# 1_Interface.net
KiCad netlist of a schematic drawn in Altium Designer
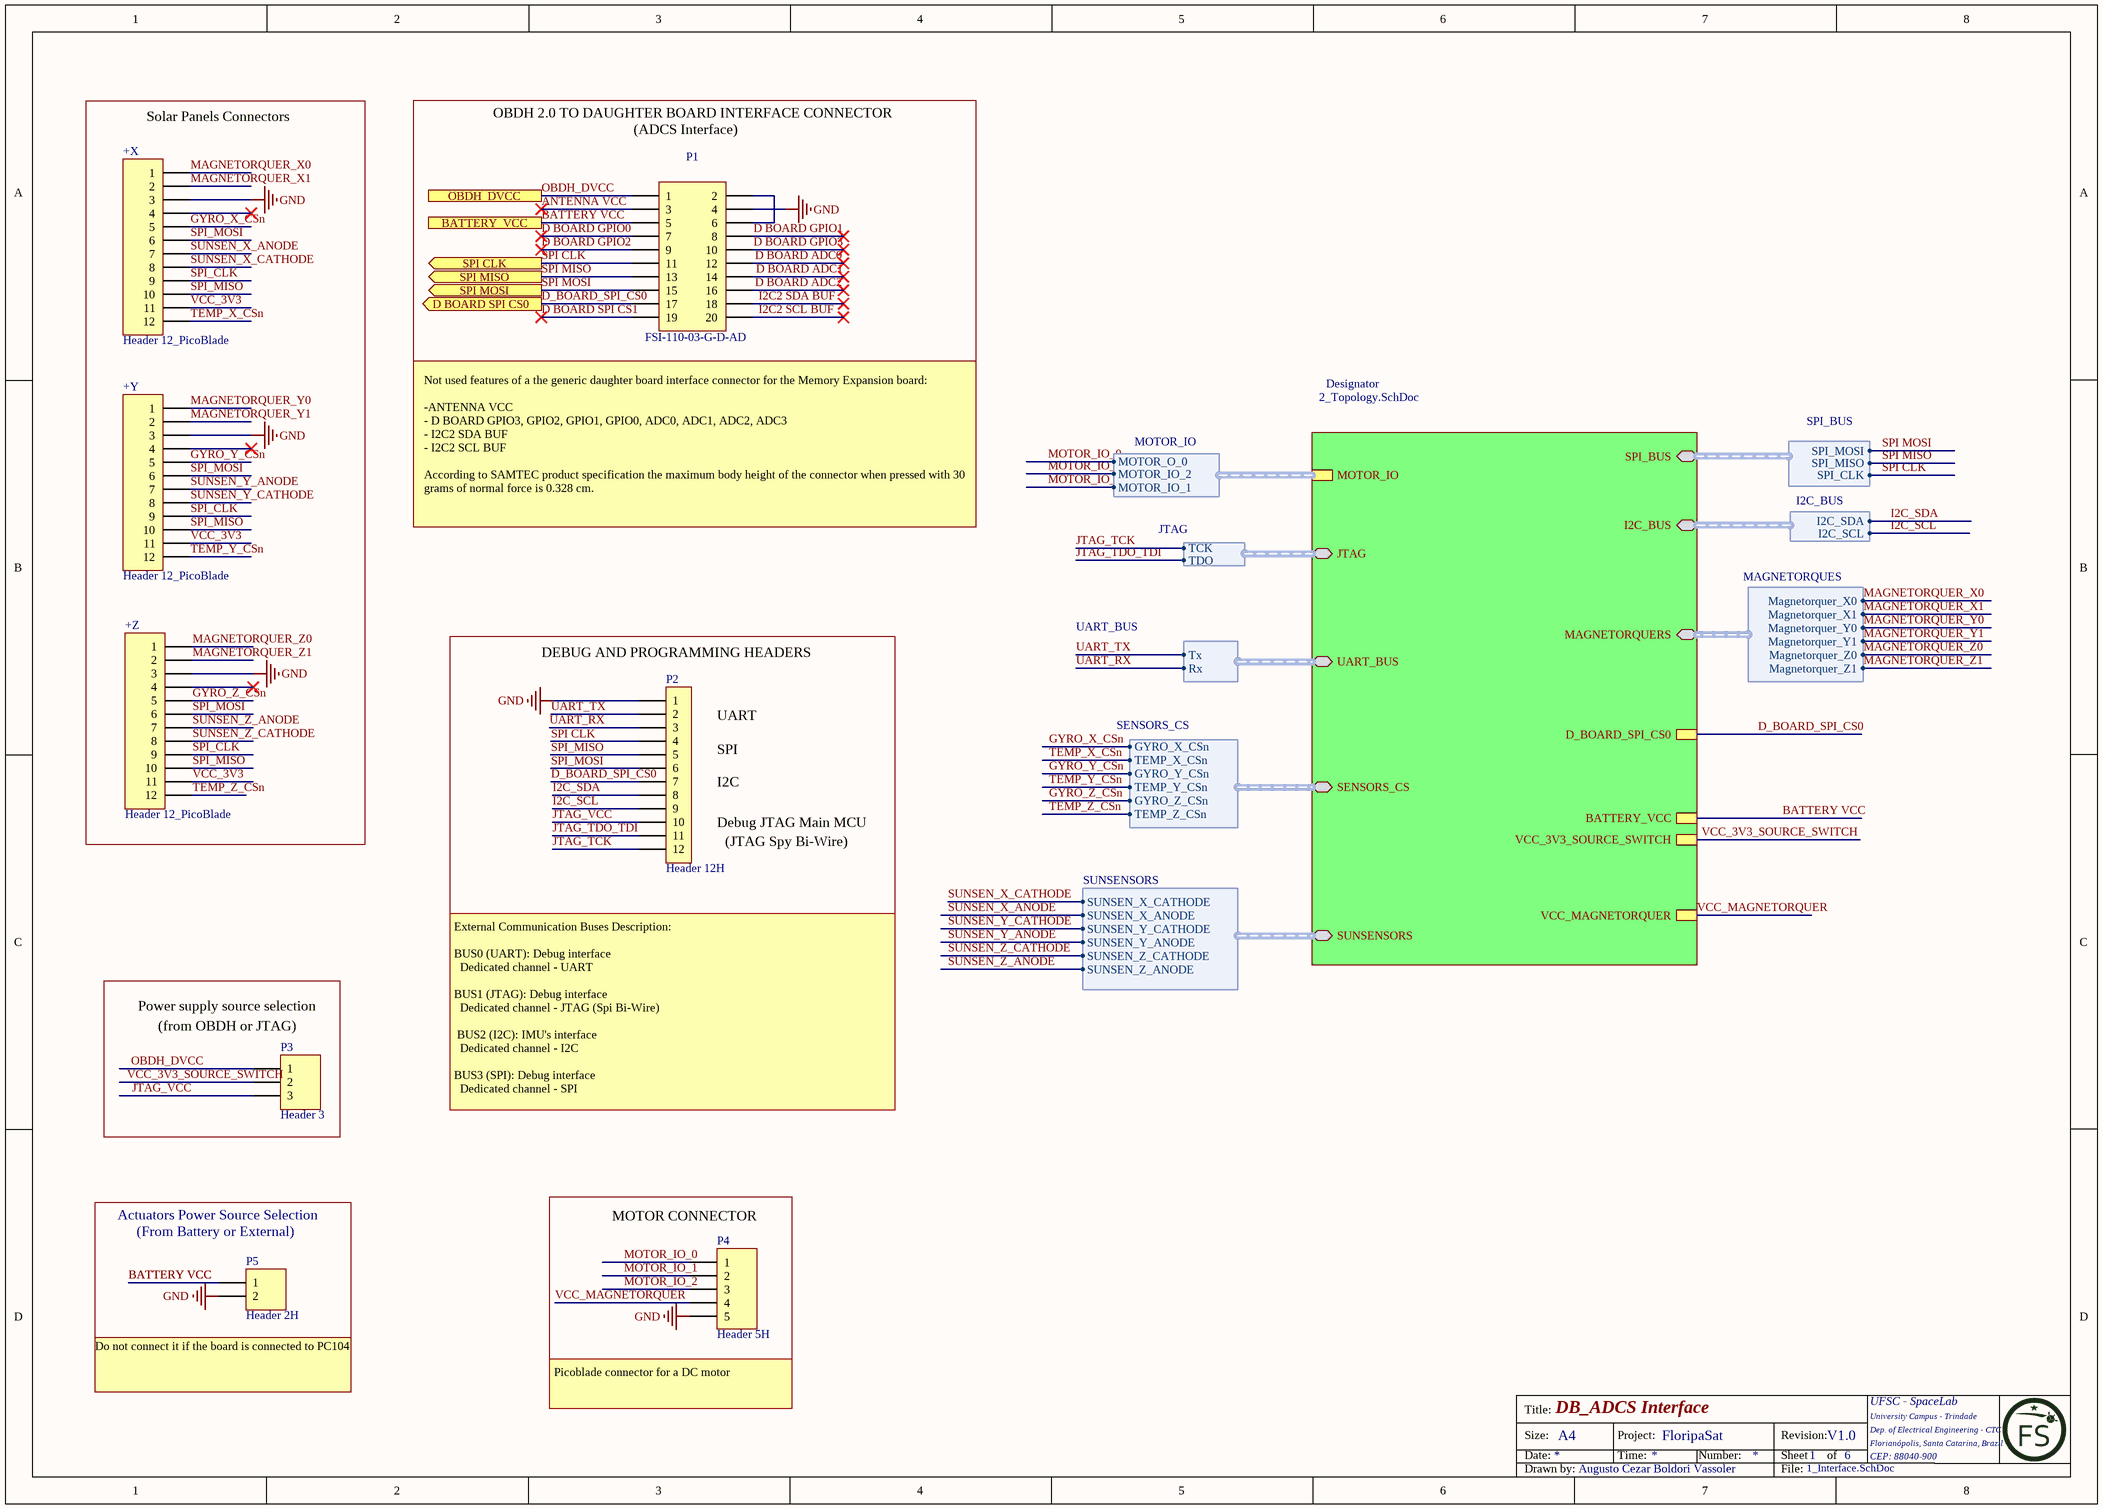
[diagram p0: 1_Interface.SchDoc]

(export (version "E")
  (design (tool "Eeschema 10.0.6"))
  (components
    (comp (ref "+X")
      (value "Header 12_PicoBlade")
      (footprint "HDR12 PicoBlade - duplicate")
      (description "Header, 12-Pin")
      (fields (field (name "PARTNUMBER") "53398-1271") (field (name "PUBLISHER") "Altium Limited"))
      (libsource (lib "FloripaSatSchlib") (part "Header 12_PicoBlade"))
    )
    (comp (ref "+Y")
      (value "Header 12_PicoBlade")
      (footprint "HDR12 PicoBlade - duplicate")
      (description "Header, 12-Pin")
      (fields (field (name "PARTNUMBER") "53398-1271") (field (name "PUBLISHER") "Altium Limited"))
      (libsource (lib "FloripaSatSchlib") (part "Header 12_PicoBlade"))
    )
    (comp (ref "+Z")
      (value "Header 12_PicoBlade")
      (footprint "HDR12 PicoBlade - duplicate")
      (description "Header, 12-Pin")
      (fields (field (name "PARTNUMBER") "533981271") (field (name "PUBLISHER") "Altium Limited"))
      (libsource (lib "FloripaSatSchlib") (part "Header 12_PicoBlade"))
    )
    (comp (ref "P1")
      (value "FSI-110-03-G-D-AD")
      (footprint "Mating FSI-110-03-G-D-AD")
      (description "CONN STACKING 20POS SMD GOLD")
      (fields (field (name "MANUFACTURER") "Samtec"))
      (libsource (lib "Memory_Expansion_Daughter_Board_SchLib") (part "FSI-110-03-G-D-AD"))
    )
    (comp (ref "P2")
      (value "Header 12H")
      (footprint "61301211021")
      (description "Header, 12")
      (fields
        (field (name "MANUFACTURER") "Wurth Electronics")
        (field (name "MANUFACTURER PART NUMBER") "61301211021")
      )
      (libsource (lib "PCB_DB_ADCS") (part "Header 12H"))
    )
    (comp (ref "P3")
      (value "Header 3")
      (footprint "HDR1X3")
      (description "Header, 3-Pin")
      (fields (field (name "PUBLISHER") "Altium Limited"))
      (libsource (lib "Miscellaneous Connectors") (part "Header 3"))
    )
    (comp (ref "P4")
      (value "Header 5H")
      (footprint "MOLX-53398-0571-5_V")
      (description "Header,5-Pin,Right Angle")
      (fields (field (name "MANUFACTURER") "Molex") (field (name "MANUFACTURER PART NUMBER") "53398-0571"))
      (libsource (lib "PCB_Eng_Model_OBDH_2") (part "Header 5H_PicoBlade"))
    )
    (comp (ref "P5")
      (value "Header 2H")
      (footprint "HDR1X2H")
      (description "Header, 2-Pin, Right Angle")
      (fields (field (name "PUBLISHER") "Altium Limited"))
      (libsource (lib "PCB_DB_ADCS") (part "Header 2H"))
    )
  )
  (nets
    (net (code "9") (name "/ANTENNA VCC") (class "Default")
      (node (ref "P1") (pin "3") (pinfunction "3_3") (pintype "passive+no_connect"))
    )
    (net (code "10") (name "/BATTERY VCC") (class "Default")
      (node (ref "P1") (pin "5") (pinfunction "5_5") (pintype "passive"))
      (node (ref "P5") (pin "1") (pinfunction "1_1") (pintype "passive"))
    )
    (net (code "11") (name "/D BOARD ADC0") (class "Default")
      (node (ref "P1") (pin "12") (pinfunction "12_12") (pintype "passive+no_connect"))
    )
    (net (code "12") (name "/D BOARD ADC1") (class "Default")
      (node (ref "P1") (pin "14") (pinfunction "14_14") (pintype "passive+no_connect"))
    )
    (net (code "13") (name "/D BOARD ADC2") (class "Default")
      (node (ref "P1") (pin "16") (pinfunction "16_16") (pintype "passive+no_connect"))
    )
    (net (code "14") (name "/D BOARD GPIO0") (class "Default")
      (node (ref "P1") (pin "7") (pinfunction "7_7") (pintype "passive+no_connect"))
    )
    (net (code "15") (name "/D BOARD GPIO1") (class "Default")
      (node (ref "P1") (pin "8") (pinfunction "8_8") (pintype "passive+no_connect"))
    )
    (net (code "16") (name "/D BOARD GPIO2") (class "Default")
      (node (ref "P1") (pin "9") (pinfunction "9_9") (pintype "passive+no_connect"))
    )
    (net (code "17") (name "/D BOARD GPIO3") (class "Default")
      (node (ref "P1") (pin "10") (pinfunction "10_10") (pintype "passive+no_connect"))
    )
    (net (code "18") (name "/D BOARD SPI CS1") (class "Default")
      (node (ref "P1") (pin "19") (pinfunction "19_19") (pintype "passive+no_connect"))
    )
    (net (code "19") (name "/D_BOARD_SPI_CS0") (class "Default")
      (node (ref "P1") (pin "17") (pinfunction "17_17") (pintype "passive"))
      (node (ref "P2") (pin "7") (pinfunction "7_7") (pintype "passive"))
    )
    (net (code "20") (name "/GYRO_X_CSn") (class "Default")
      (node (ref "+X") (pin "5") (pinfunction "5_5") (pintype "passive"))
    )
    (net (code "21") (name "/GYRO_Y_CSn") (class "Default")
      (node (ref "+Y") (pin "5") (pinfunction "5_5") (pintype "passive"))
    )
    (net (code "22") (name "/GYRO_Z_CSn") (class "Default")
      (node (ref "+Z") (pin "5") (pinfunction "5_5") (pintype "passive"))
    )
    (net (code "23") (name "/I2C2 SCL BUF") (class "Default")
      (node (ref "P1") (pin "20") (pinfunction "20_20") (pintype "passive+no_connect"))
    )
    (net (code "24") (name "/I2C2 SDA BUF") (class "Default")
      (node (ref "P1") (pin "18") (pinfunction "18_18") (pintype "passive+no_connect"))
    )
    (net (code "25") (name "/I2C_SCL") (class "Default")
      (node (ref "P2") (pin "9") (pinfunction "9_9") (pintype "passive"))
    )
    (net (code "26") (name "/I2C_SDA") (class "Default")
      (node (ref "P2") (pin "8") (pinfunction "8_8") (pintype "passive"))
    )
    (net (code "27") (name "/JTAG_TCK") (class "Default")
      (node (ref "P2") (pin "12") (pinfunction "12_12") (pintype "passive"))
    )
    (net (code "28") (name "/JTAG_TDO_TDI") (class "Default")
      (node (ref "P2") (pin "11") (pinfunction "11_11") (pintype "passive"))
    )
    (net (code "29") (name "/JTAG_VCC") (class "Default")
      (node (ref "P2") (pin "10") (pinfunction "10_10") (pintype "passive"))
      (node (ref "P3") (pin "3") (pinfunction "3_3") (pintype "passive"))
    )
    (net (code "30") (name "/MAGNETORQUER_X0") (class "Default")
      (node (ref "+X") (pin "1") (pinfunction "1_1") (pintype "passive"))
    )
    (net (code "31") (name "/MAGNETORQUER_X1") (class "Default")
      (node (ref "+X") (pin "2") (pinfunction "2_2") (pintype "passive"))
    )
    (net (code "32") (name "/MAGNETORQUER_Y0") (class "Default")
      (node (ref "+Y") (pin "1") (pinfunction "1_1") (pintype "passive"))
    )
    (net (code "33") (name "/MAGNETORQUER_Y1") (class "Default")
      (node (ref "+Y") (pin "2") (pinfunction "2_2") (pintype "passive"))
    )
    (net (code "34") (name "/MAGNETORQUER_Z0") (class "Default")
      (node (ref "+Z") (pin "1") (pinfunction "1_1") (pintype "passive"))
    )
    (net (code "35") (name "/MAGNETORQUER_Z1") (class "Default")
      (node (ref "+Z") (pin "2") (pinfunction "2_2") (pintype "passive"))
    )
    (net (code "36") (name "/MOTOR_IO_0") (class "Default")
      (node (ref "P4") (pin "1") (pinfunction "1_1") (pintype "passive"))
    )
    (net (code "37") (name "/MOTOR_IO_1") (class "Default")
      (node (ref "P4") (pin "2") (pinfunction "2_2") (pintype "passive"))
    )
    (net (code "38") (name "/MOTOR_IO_2") (class "Default")
      (node (ref "P4") (pin "3") (pinfunction "3_3") (pintype "passive"))
    )
    (net (code "39") (name "/OBDH_DVCC") (class "Default")
      (node (ref "P1") (pin "1") (pinfunction "1_1") (pintype "passive"))
      (node (ref "P3") (pin "1") (pinfunction "1_1") (pintype "passive"))
    )
    (net (code "40") (name "/SPI CLK") (class "Default")
      (node (ref "P1") (pin "11") (pinfunction "11_11") (pintype "passive"))
      (node (ref "P2") (pin "4") (pinfunction "4_4") (pintype "passive"))
    )
    (net (code "41") (name "/SPI MISO") (class "Default")
      (node (ref "P1") (pin "13") (pinfunction "13_13") (pintype "passive"))
    )
    (net (code "42") (name "/SPI MOSI") (class "Default")
      (node (ref "P1") (pin "15") (pinfunction "15_15") (pintype "passive"))
    )
    (net (code "43") (name "/SPI_CLK") (class "Default")
      (node (ref "+X") (pin "9") (pinfunction "9_9") (pintype "passive"))
      (node (ref "+Y") (pin "9") (pinfunction "9_9") (pintype "passive"))
      (node (ref "+Z") (pin "9") (pinfunction "9_9") (pintype "passive"))
    )
    (net (code "44") (name "/SPI_MISO") (class "Default")
      (node (ref "+X") (pin "10") (pinfunction "10_10") (pintype "passive"))
      (node (ref "+Y") (pin "10") (pinfunction "10_10") (pintype "passive"))
      (node (ref "+Z") (pin "10") (pinfunction "10_10") (pintype "passive"))
      (node (ref "P2") (pin "5") (pinfunction "5_5") (pintype "passive"))
    )
    (net (code "45") (name "/SPI_MOSI") (class "Default")
      (node (ref "+X") (pin "6") (pinfunction "6_6") (pintype "passive"))
      (node (ref "+Y") (pin "6") (pinfunction "6_6") (pintype "passive"))
      (node (ref "+Z") (pin "6") (pinfunction "6_6") (pintype "passive"))
      (node (ref "P2") (pin "6") (pinfunction "6_6") (pintype "passive"))
    )
    (net (code "46") (name "/SUNSEN_X_ANODE") (class "Default")
      (node (ref "+X") (pin "7") (pinfunction "7_7") (pintype "passive"))
    )
    (net (code "47") (name "/SUNSEN_X_CATHODE") (class "Default")
      (node (ref "+X") (pin "8") (pinfunction "8_8") (pintype "passive"))
    )
    (net (code "48") (name "/SUNSEN_Y_ANODE") (class "Default")
      (node (ref "+Y") (pin "7") (pinfunction "7_7") (pintype "passive"))
    )
    (net (code "49") (name "/SUNSEN_Y_CATHODE") (class "Default")
      (node (ref "+Y") (pin "8") (pinfunction "8_8") (pintype "passive"))
    )
    (net (code "50") (name "/SUNSEN_Z_ANODE") (class "Default")
      (node (ref "+Z") (pin "7") (pinfunction "7_7") (pintype "passive"))
    )
    (net (code "51") (name "/SUNSEN_Z_CATHODE") (class "Default")
      (node (ref "+Z") (pin "8") (pinfunction "8_8") (pintype "passive"))
    )
    (net (code "52") (name "/TEMP_X_CSn") (class "Default")
      (node (ref "+X") (pin "12") (pinfunction "12_12") (pintype "passive"))
    )
    (net (code "53") (name "/TEMP_Y_CSn") (class "Default")
      (node (ref "+Y") (pin "12") (pinfunction "12_12") (pintype "passive"))
    )
    (net (code "54") (name "/TEMP_Z_CSn") (class "Default")
      (node (ref "+Z") (pin "12") (pinfunction "12_12") (pintype "passive"))
    )
    (net (code "55") (name "/UART_RX") (class "Default")
      (node (ref "P2") (pin "3") (pinfunction "3_3") (pintype "passive"))
    )
    (net (code "56") (name "/UART_TX") (class "Default")
      (node (ref "P2") (pin "2") (pinfunction "2_2") (pintype "passive"))
    )
    (net (code "57") (name "/VCC_3V3") (class "Default")
      (node (ref "+X") (pin "11") (pinfunction "11_11") (pintype "passive"))
      (node (ref "+Y") (pin "11") (pinfunction "11_11") (pintype "passive"))
      (node (ref "+Z") (pin "11") (pinfunction "11_11") (pintype "passive"))
    )
    (net (code "58") (name "/VCC_3V3_SOURCE_SWITCH") (class "Default")
      (node (ref "P3") (pin "2") (pinfunction "2_2") (pintype "passive"))
    )
    (net (code "59") (name "/VCC_MAGNETORQUER") (class "Default")
      (node (ref "P4") (pin "4") (pinfunction "4_4") (pintype "passive"))
    )
    (net (code "68") (name "GND") (class "Default")
      (node (ref "+X") (pin "3") (pinfunction "3_3") (pintype "passive"))
      (node (ref "+Y") (pin "3") (pinfunction "3_3") (pintype "passive"))
      (node (ref "+Z") (pin "3") (pinfunction "3_3") (pintype "passive"))
      (node (ref "P1") (pin "4") (pinfunction "4_4") (pintype "passive"))
      (node (ref "P2") (pin "1") (pinfunction "1_1") (pintype "passive"))
      (node (ref "P4") (pin "5") (pinfunction "5_5") (pintype "passive"))
      (node (ref "P5") (pin "2") (pinfunction "2_2") (pintype "passive"))
    )
    (net (code "69") (name "Net-(P1-Pad2)") (class "Default")
      (node (ref "P1") (pin "2") (pinfunction "2_2") (pintype "passive"))
      (node (ref "P1") (pin "6") (pinfunction "6_6") (pintype "passive"))
    )
    (net (code "70") (name "unconnected-(+X-Pad4)") (class "Default")
      (node (ref "+X") (pin "4") (pinfunction "4_4") (pintype "passive+no_connect"))
    )
    (net (code "71") (name "unconnected-(+Y-Pad4)") (class "Default")
      (node (ref "+Y") (pin "4") (pinfunction "4_4") (pintype "passive+no_connect"))
    )
    (net (code "72") (name "unconnected-(+Z-Pad4)") (class "Default")
      (node (ref "+Z") (pin "4") (pinfunction "4_4") (pintype "passive+no_connect"))
    )
  )
)
